# Collecteur_Estomac_Yeux_Bouche.net
KiCad netlist of a schematic drawn in EasyEDA
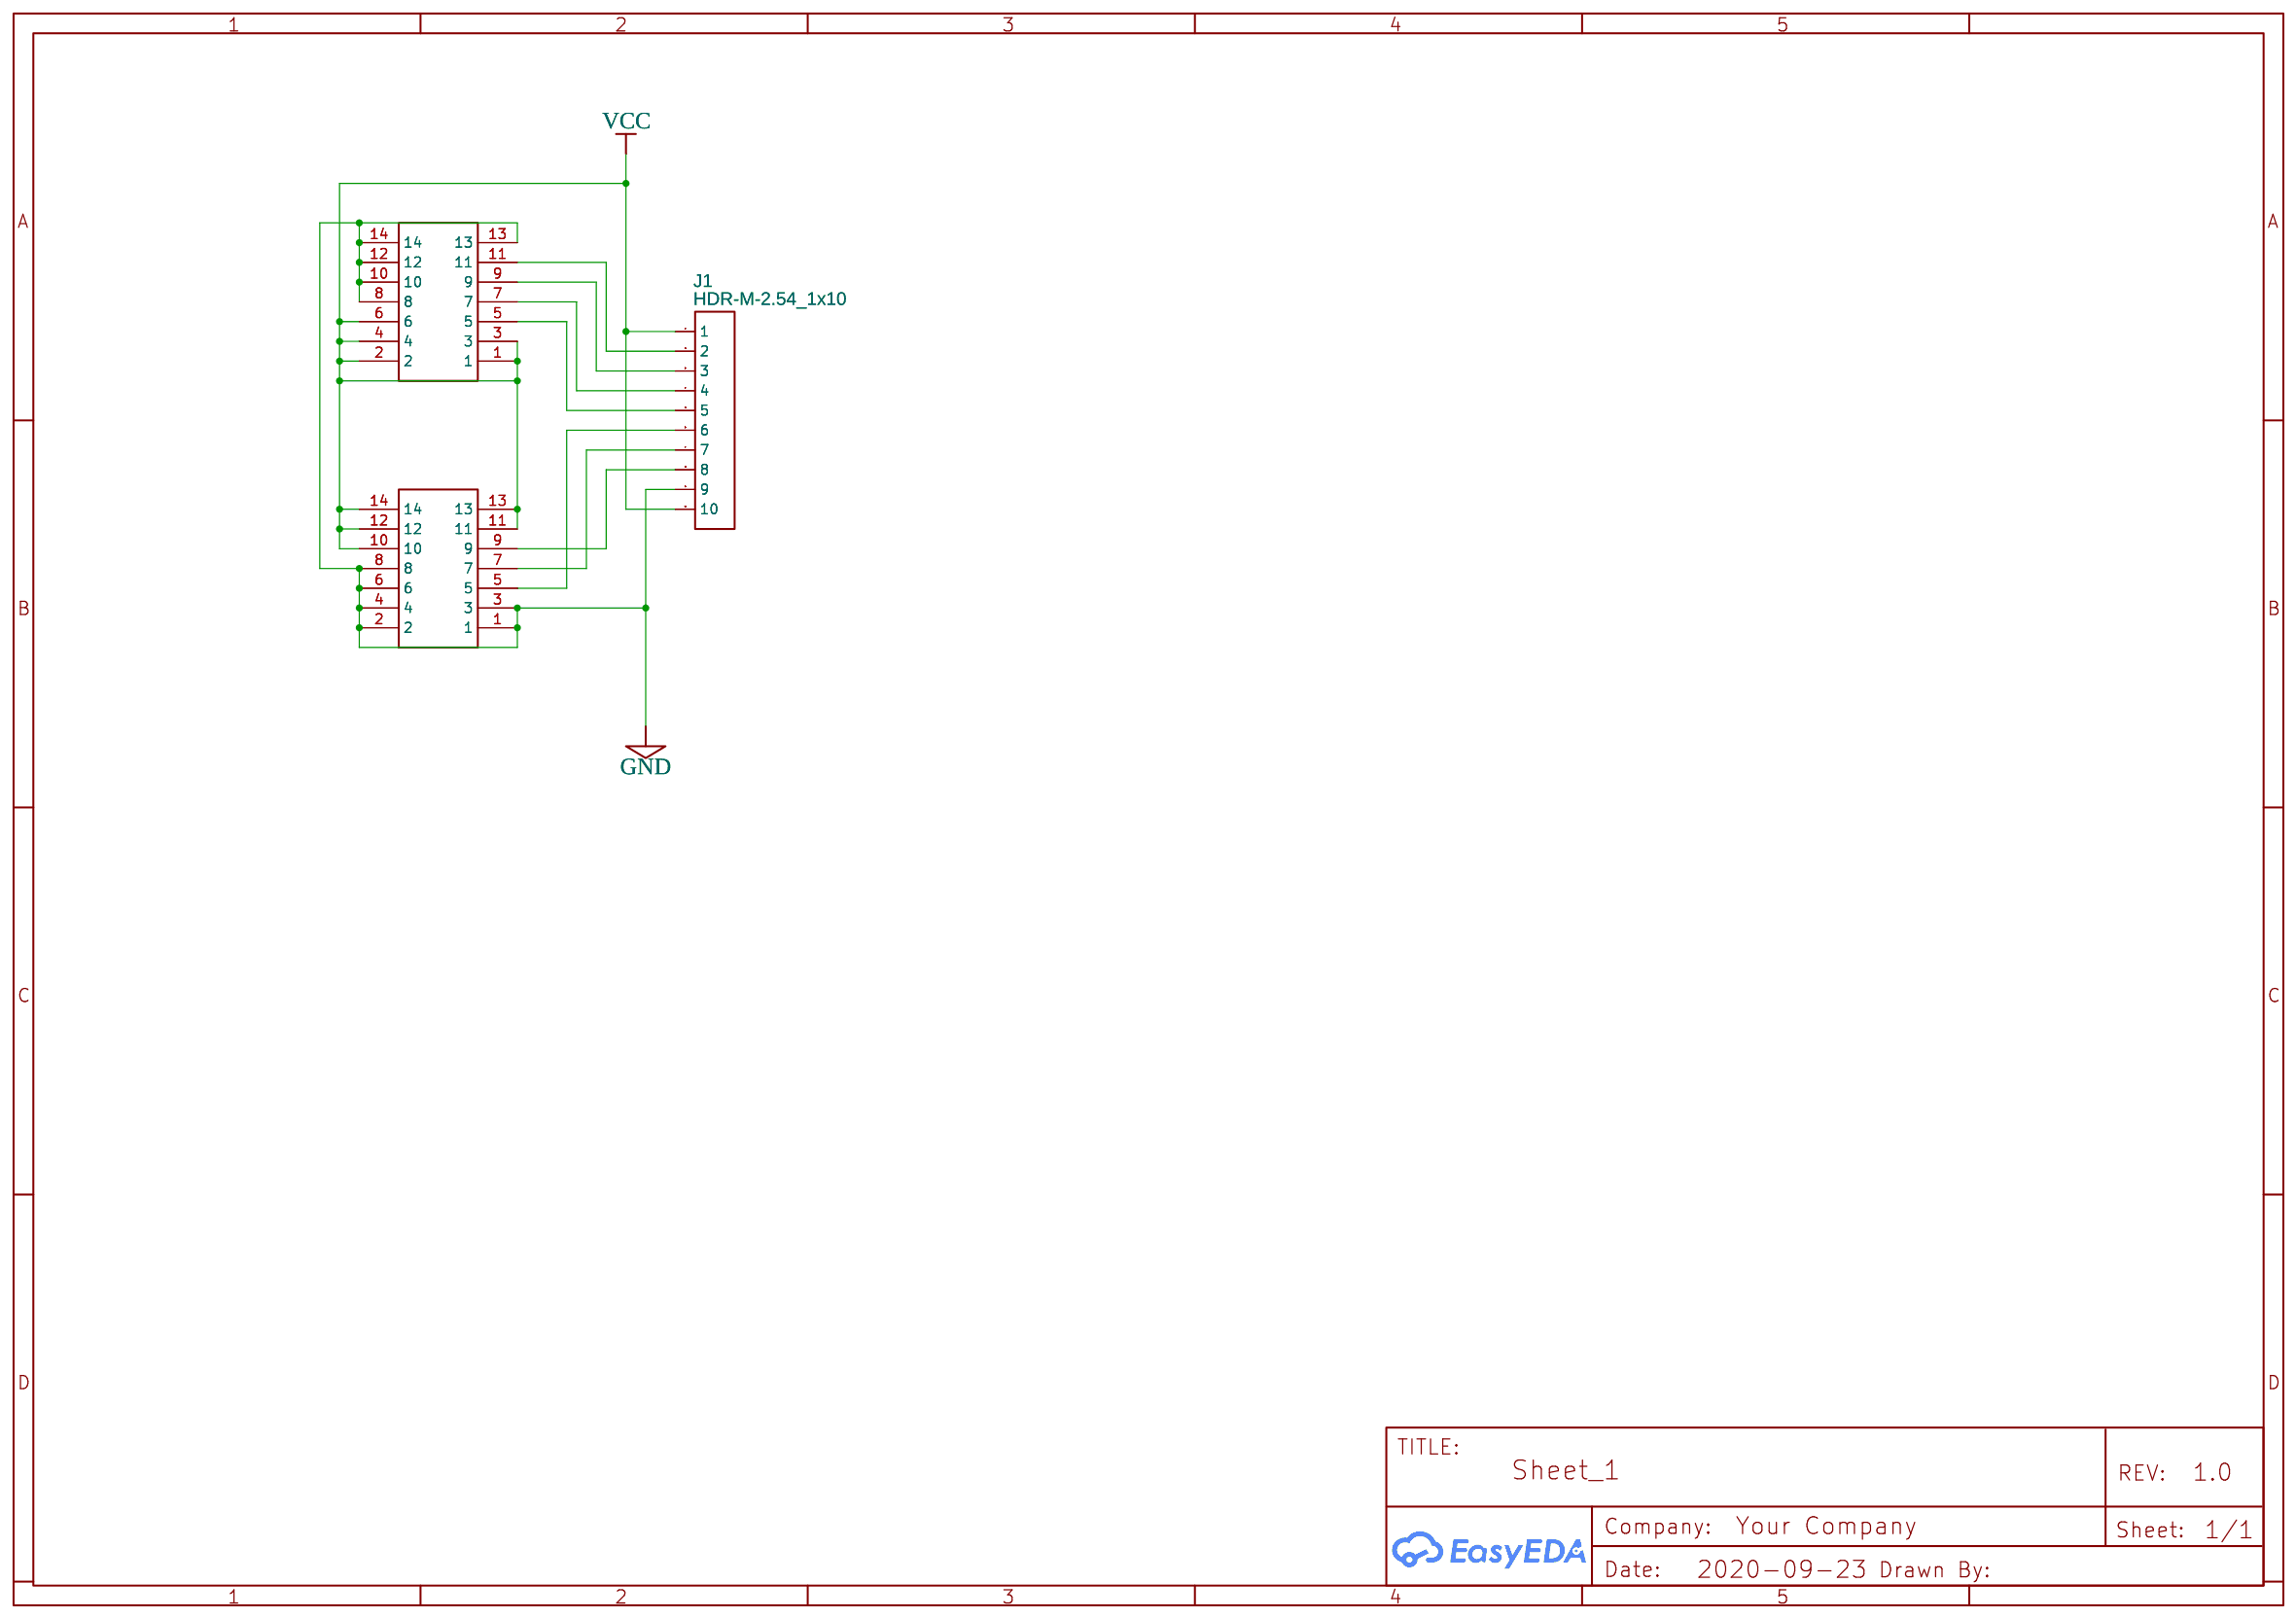
[diagram p0: schematic sheet]

(export (version "E")
  (design (tool "Eeschema 10.0.6"))
  (components
    (comp (ref "J1")
      (value "HDR-M-2.54_1x10")
      (fields (field (name "BOM_Supplier Part") "C57369"))
      (libsource (lib "") (part "HDR-M-2.54_1x10"))
    )
    (comp (ref "OUT1")
      (value "Horn connector/2.0mm2*7P")
      (fields
        (field (name "BOM_Manufacturer Part") "Horn connector/2.0mm2*7P直简牛")
        (field (name "BOM_Supplier Part") "C29428")
      )
      (libsource (lib "") (part "Horn connector/2.0mm2*7P"))
    )
    (comp (ref "OUT3")
      (value "Horn connector/2.0mm2*7P")
      (fields
        (field (name "BOM_Manufacturer Part") "Horn connector/2.0mm2*7P直简牛")
        (field (name "BOM_Supplier Part") "C29428")
      )
      (libsource (lib "") (part "Horn connector/2.0mm2*7P"))
    )
  )
  (nets
    (net (code "1") (name "GND") (class "Default")
      (node (ref "J1") (pin "9") (pinfunction "9_9") (pintype "unspecified"))
      (node (ref "OUT1") (pin "1") (pinfunction "1_1") (pintype "unspecified"))
      (node (ref "OUT1") (pin "2") (pinfunction "2_2") (pintype "unspecified"))
      (node (ref "OUT1") (pin "3") (pinfunction "3_3") (pintype "unspecified"))
      (node (ref "OUT1") (pin "4") (pinfunction "4_4") (pintype "unspecified"))
      (node (ref "OUT1") (pin "6") (pinfunction "6_6") (pintype "unspecified"))
      (node (ref "OUT1") (pin "8") (pinfunction "8_8") (pintype "unspecified"))
      (node (ref "OUT3") (pin "10") (pinfunction "10_10") (pintype "unspecified"))
      (node (ref "OUT3") (pin "12") (pinfunction "12_12") (pintype "unspecified"))
      (node (ref "OUT3") (pin "13") (pinfunction "13_13") (pintype "unspecified"))
      (node (ref "OUT3") (pin "14") (pinfunction "14_14") (pintype "unspecified"))
      (node (ref "OUT3") (pin "8") (pinfunction "8_8") (pintype "unspecified"))
    )
    (net (code "2") (name "Net-(J1-Pad2)") (class "Default")
      (node (ref "J1") (pin "2") (pinfunction "2_2") (pintype "unspecified"))
      (node (ref "OUT3") (pin "11") (pinfunction "11_11") (pintype "unspecified"))
    )
    (net (code "3") (name "Net-(J1-Pad3)") (class "Default")
      (node (ref "J1") (pin "3") (pinfunction "3_3") (pintype "unspecified"))
      (node (ref "OUT3") (pin "9") (pinfunction "9_9") (pintype "unspecified"))
    )
    (net (code "4") (name "Net-(J1-Pad4)") (class "Default")
      (node (ref "J1") (pin "4") (pinfunction "4_4") (pintype "unspecified"))
      (node (ref "OUT3") (pin "7") (pinfunction "7_7") (pintype "unspecified"))
    )
    (net (code "5") (name "Net-(J1-Pad5)") (class "Default")
      (node (ref "J1") (pin "5") (pinfunction "5_5") (pintype "unspecified"))
      (node (ref "OUT3") (pin "5") (pinfunction "5_5") (pintype "unspecified"))
    )
    (net (code "6") (name "Net-(J1-Pad6)") (class "Default")
      (node (ref "J1") (pin "6") (pinfunction "6_6") (pintype "unspecified"))
      (node (ref "OUT1") (pin "5") (pinfunction "5_5") (pintype "unspecified"))
    )
    (net (code "7") (name "Net-(J1-Pad7)") (class "Default")
      (node (ref "J1") (pin "7") (pinfunction "7_7") (pintype "unspecified"))
      (node (ref "OUT1") (pin "7") (pinfunction "7_7") (pintype "unspecified"))
    )
    (net (code "8") (name "Net-(J1-Pad8)") (class "Default")
      (node (ref "J1") (pin "8") (pinfunction "8_8") (pintype "unspecified"))
      (node (ref "OUT1") (pin "9") (pinfunction "9_9") (pintype "unspecified"))
    )
    (net (code "9") (name "VCC") (class "Default")
      (node (ref "J1") (pin "1") (pinfunction "1_1") (pintype "unspecified"))
      (node (ref "J1") (pin "10") (pinfunction "10_10") (pintype "unspecified"))
      (node (ref "OUT1") (pin "10") (pinfunction "10_10") (pintype "unspecified"))
      (node (ref "OUT1") (pin "11") (pinfunction "11_11") (pintype "unspecified"))
      (node (ref "OUT1") (pin "12") (pinfunction "12_12") (pintype "unspecified"))
      (node (ref "OUT1") (pin "13") (pinfunction "13_13") (pintype "unspecified"))
      (node (ref "OUT1") (pin "14") (pinfunction "14_14") (pintype "unspecified"))
      (node (ref "OUT3") (pin "1") (pinfunction "1_1") (pintype "unspecified"))
      (node (ref "OUT3") (pin "2") (pinfunction "2_2") (pintype "unspecified"))
      (node (ref "OUT3") (pin "3") (pinfunction "3_3") (pintype "unspecified"))
      (node (ref "OUT3") (pin "4") (pinfunction "4_4") (pintype "unspecified"))
      (node (ref "OUT3") (pin "6") (pinfunction "6_6") (pintype "unspecified"))
    )
  )
)
